# Reg-LT.net
KiCad netlist of a schematic drawn in EAGLE
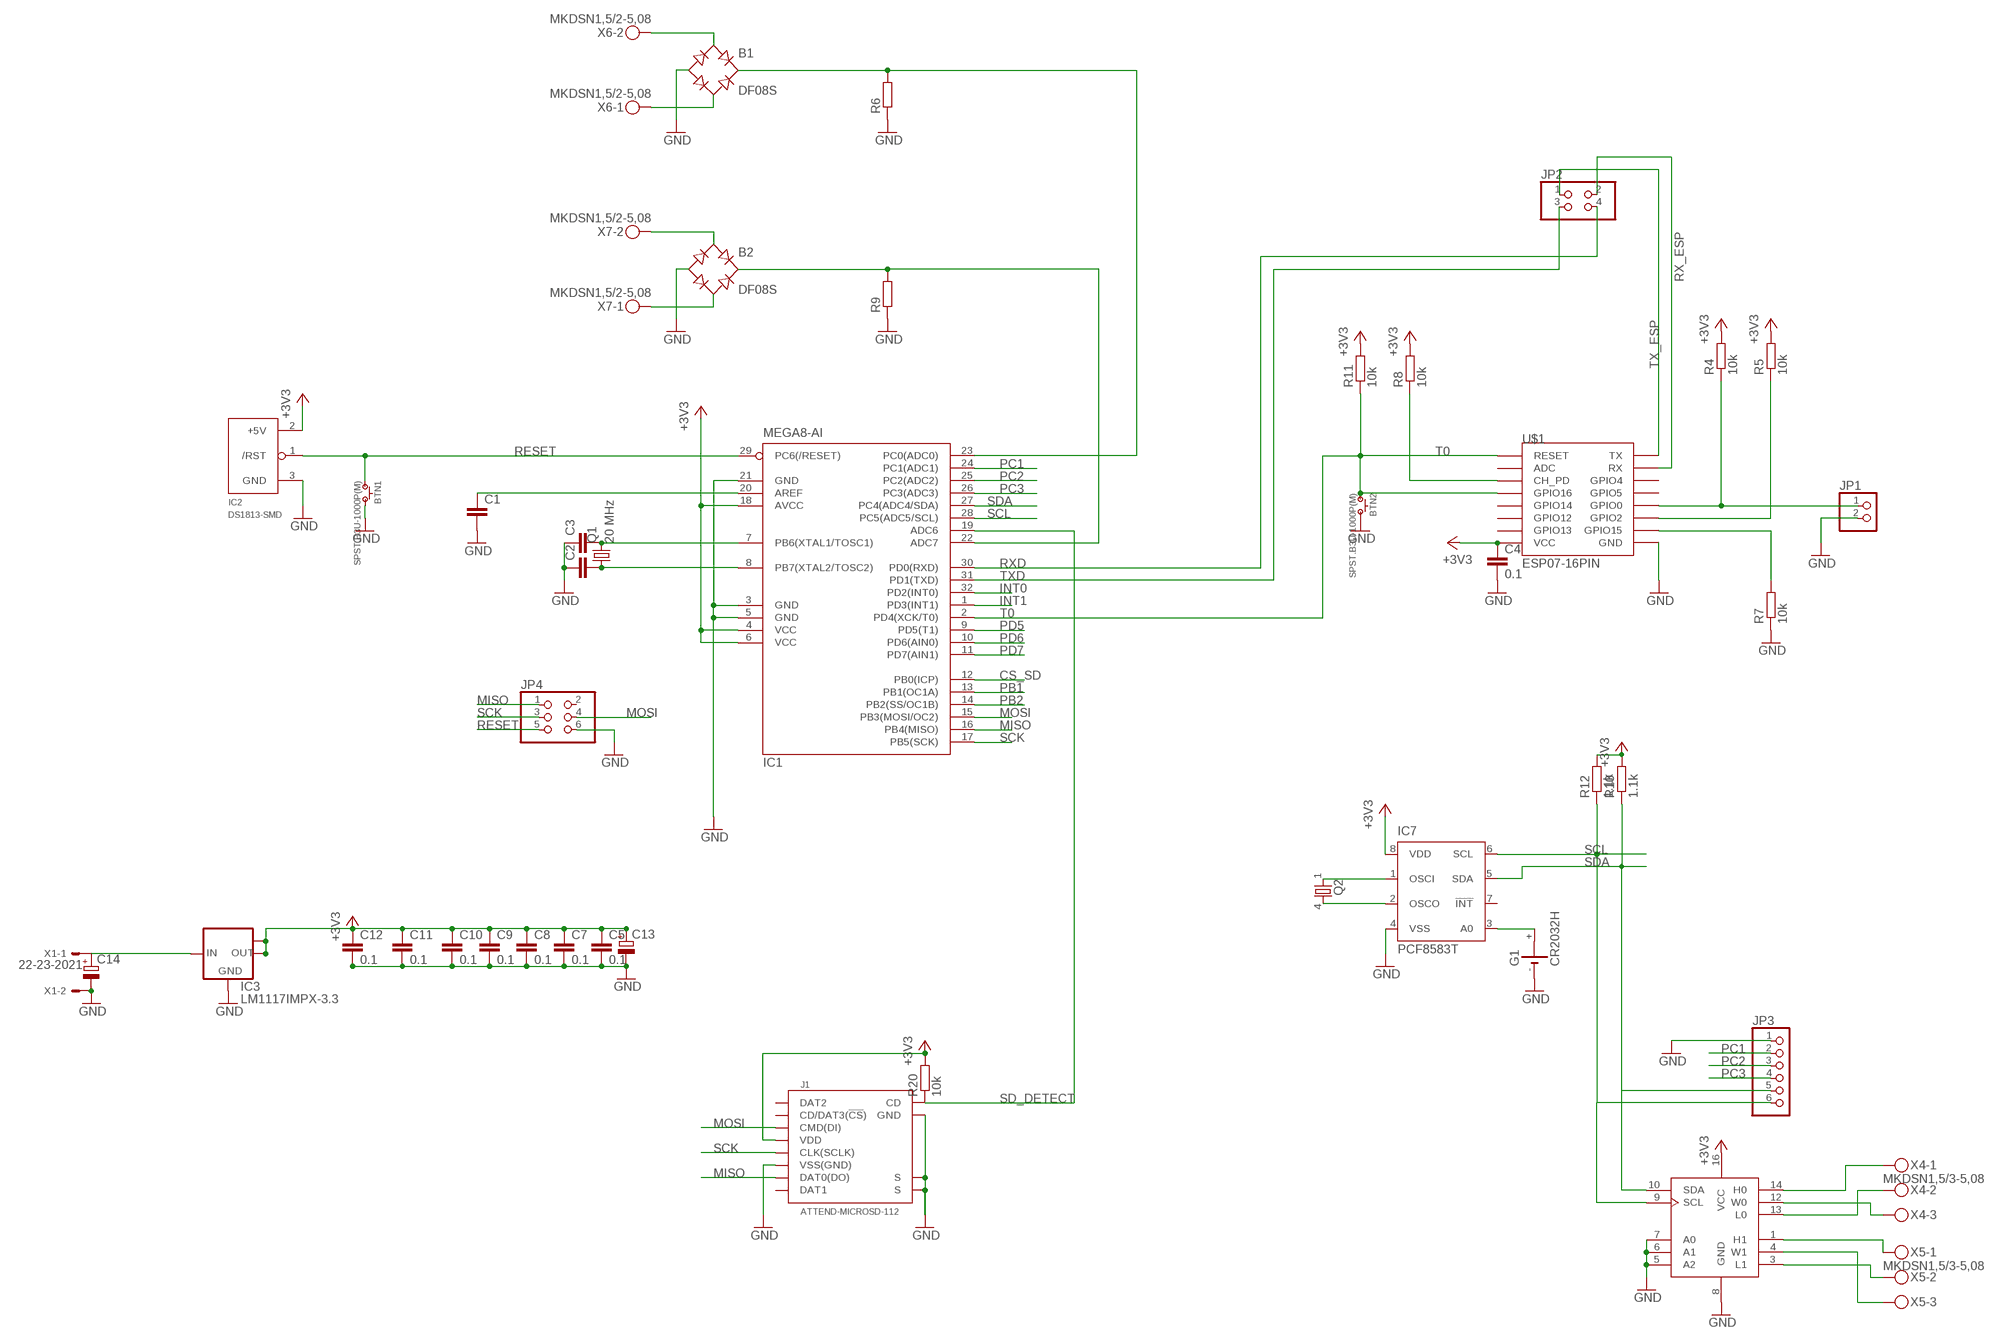
[diagram p0: schematic, sheet 1]

(export (version "E")
  (design (tool "Eeschema 10.0.6"))
  (components
    (comp (ref "B1")
      (value "DF08S")
      (footprint "eagle-import:DFS")
      (libsource (lib "eagle-import") (part "DFS08"))
    )
    (comp (ref "B2")
      (value "DF08S")
      (footprint "eagle-import:DFS")
      (libsource (lib "eagle-import") (part "DFS08"))
    )
    (comp (ref "BTN1")
      (value "SPST.B3U-1000P(M)")
      (footprint "eagle-import:B3U-1000P(M)")
      (libsource (lib "eagle-import") (part "SPST.B3U-1000P(M)"))
    )
    (comp (ref "BTN2")
      (value "SPST.B3U-1000P(M)")
      (footprint "eagle-import:B3U-1000P(M)")
      (libsource (lib "eagle-import") (part "SPST.B3U-1000P(M)"))
    )
    (comp (ref "C1")
      (value "C-EUC0805K")
      (footprint "eagle-import:C0805K")
      (libsource (lib "eagle-import") (part "C-EUC0805K"))
    )
    (comp (ref "C2")
      (value "C-EUC0805")
      (footprint "eagle-import:C0805")
      (libsource (lib "eagle-import") (part "C-EUC0805"))
    )
    (comp (ref "C3")
      (value "C-EUC0805")
      (footprint "eagle-import:C0805")
      (libsource (lib "eagle-import") (part "C-EUC0805"))
    )
    (comp (ref "C4")
      (value "0.1")
      (footprint "eagle-import:C0805")
      (libsource (lib "eagle-import") (part "C-EUC0805"))
    )
    (comp (ref "C5")
      (value "0.1")
      (footprint "eagle-import:C0805")
      (libsource (lib "eagle-import") (part "C-EUC0805"))
    )
    (comp (ref "C7")
      (value "0.1")
      (footprint "eagle-import:C0805")
      (libsource (lib "eagle-import") (part "C-EUC0805"))
    )
    (comp (ref "C8")
      (value "0.1")
      (footprint "eagle-import:C0805")
      (libsource (lib "eagle-import") (part "C-EUC0805"))
    )
    (comp (ref "C9")
      (value "0.1")
      (footprint "eagle-import:C0805")
      (libsource (lib "eagle-import") (part "C-EUC0805"))
    )
    (comp (ref "C10")
      (value "0.1")
      (footprint "eagle-import:C0805")
      (libsource (lib "eagle-import") (part "C-EUC0805"))
    )
    (comp (ref "C11")
      (value "0.1")
      (footprint "eagle-import:C0805")
      (libsource (lib "eagle-import") (part "C-EUC0805"))
    )
    (comp (ref "C12")
      (value "0.1")
      (footprint "eagle-import:C0805")
      (libsource (lib "eagle-import") (part "C-EUC0805"))
    )
    (comp (ref "C13")
      (value "CPOL-EU153CLV-0605")
      (footprint "eagle-import:153CLV-0605")
      (libsource (lib "eagle-import") (part "CPOL-EU153CLV-0605"))
    )
    (comp (ref "C14")
      (value "CPOL-EU153CLV-0605")
      (footprint "eagle-import:153CLV-0605")
      (libsource (lib "eagle-import") (part "CPOL-EU153CLV-0605"))
    )
    (comp (ref "G1")
      (value "CR2032H")
      (footprint "eagle-import:CR2032H")
      (libsource (lib "eagle-import") (part "CR2032H"))
    )
    (comp (ref "IC1")
      (value "MEGA8-AI")
      (footprint "eagle-import:TQFP32-08")
      (fields (field (name "MPN") "ATMEGA8-16AU"))
      (libsource (lib "eagle-import") (part "MEGA8-AI"))
    )
    (comp (ref "IC2")
      (value "DS1813-SMD")
      (footprint "eagle-import:SOT-23")
      (libsource (lib "eagle-import") (part "DS1813-SMD"))
    )
    (comp (ref "IC3")
      (value "LM1117IMPX-3.3")
      (footprint "eagle-import:SOT223")
      (libsource (lib "eagle-import") (part "LM1117IMPX-3.3"))
    )
    (comp (ref "IC7")
      (value "PCF8583T")
      (footprint "eagle-import:SO8-7_5")
      (libsource (lib "eagle-import") (part "PCF8583T"))
    )
    (comp (ref "J1")
      (value "ATTEND-MICROSD-112")
      (footprint "eagle-import:ATTEND-112")
      (libsource (lib "eagle-import") (part "ATTEND-MICROSD-112"))
    )
    (comp (ref "JP1")
      (value "PINHD-1X2")
      (footprint "eagle-import:1X02")
      (libsource (lib "eagle-import") (part "PINHD-1X2"))
    )
    (comp (ref "JP2")
      (value "PINHD-2X2")
      (footprint "eagle-import:2X02")
      (libsource (lib "eagle-import") (part "PINHD-2X2"))
    )
    (comp (ref "JP3")
      (value "PINHD-1X6")
      (footprint "eagle-import:1X06")
      (libsource (lib "eagle-import") (part "PINHD-1X6"))
    )
    (comp (ref "JP4")
      (value "PINHD-2X3")
      (footprint "eagle-import:2X03")
      (libsource (lib "eagle-import") (part "PINHD-2X3"))
    )
    (comp (ref "Q1")
      (value "20 MHz")
      (footprint "eagle-import:SM49")
      (libsource (lib "eagle-import") (part "CRYSTALSM49"))
    )
    (comp (ref "Q2")
      (value "MA306")
      (footprint "eagle-import:MA306")
      (libsource (lib "eagle-import") (part "MA306"))
    )
    (comp (ref "R4")
      (value "10k")
      (footprint "eagle-import:R0805")
      (libsource (lib "eagle-import") (part "R-EU_R0805"))
    )
    (comp (ref "R5")
      (value "10k")
      (footprint "eagle-import:R0805")
      (libsource (lib "eagle-import") (part "R-EU_R0805"))
    )
    (comp (ref "R6")
      (value "R-EU_VMTA55")
      (footprint "eagle-import:VMTA55")
      (libsource (lib "eagle-import") (part "R-EU_VMTA55"))
    )
    (comp (ref "R7")
      (value "10k")
      (footprint "eagle-import:R0805")
      (libsource (lib "eagle-import") (part "R-EU_R0805"))
    )
    (comp (ref "R8")
      (value "10k")
      (footprint "eagle-import:R0805")
      (libsource (lib "eagle-import") (part "R-EU_R0805"))
    )
    (comp (ref "R9")
      (value "R-EU_VMTA55")
      (footprint "eagle-import:VMTA55")
      (libsource (lib "eagle-import") (part "R-EU_VMTA55"))
    )
    (comp (ref "R10")
      (value "1.1k")
      (footprint "eagle-import:R0805")
      (libsource (lib "eagle-import") (part "R-EU_R0805"))
    )
    (comp (ref "R11")
      (value "10k")
      (footprint "eagle-import:R0805")
      (libsource (lib "eagle-import") (part "R-EU_R0805"))
    )
    (comp (ref "R12")
      (value "1.1k")
      (footprint "eagle-import:R0805")
      (libsource (lib "eagle-import") (part "R-EU_R0805"))
    )
    (comp (ref "R20")
      (value "10k")
      (footprint "eagle-import:R0805")
      (libsource (lib "eagle-import") (part "R-EU_R0805"))
    )
    (comp (ref "U$1")
      (value "ESP07-16PIN")
      (footprint "eagle-import:ESP07-16PIN")
      (libsource (lib "eagle-import") (part "ESP07-16PIN"))
    )
    (comp (ref "U$5")
      (value "DS1803ZSO16")
      (footprint "eagle-import:SO16")
      (libsource (lib "eagle-import") (part "DS1803ZSO16"))
    )
    (comp (ref "X1")
      (value "22-23-2021")
      (footprint "eagle-import:22-23-2021")
      (fields (field (name "MF") "MOLEX"))
      (libsource (lib "eagle-import") (part "22-23-2021"))
    )
    (comp (ref "X4")
      (value "MKDSN1,5/3-5,08")
      (footprint "eagle-import:MKDSN1,5_3-5,08")
      (libsource (lib "eagle-import") (part "MKDSN1,5/3-5,08"))
    )
    (comp (ref "X5")
      (value "MKDSN1,5/3-5,08")
      (footprint "eagle-import:MKDSN1,5_3-5,08")
      (libsource (lib "eagle-import") (part "MKDSN1,5/3-5,08"))
    )
    (comp (ref "X6")
      (value "MKDSN1,5/2-5,08")
      (footprint "eagle-import:MKDSN1,5_2-5,08")
      (libsource (lib "eagle-import") (part "MKDSN1,5/2-5,08"))
    )
    (comp (ref "X7")
      (value "MKDSN1,5/2-5,08")
      (footprint "eagle-import:MKDSN1,5_2-5,08")
      (libsource (lib "eagle-import") (part "MKDSN1,5/2-5,08"))
    )
  )
  (nets
    (net (code "1") (name "+3V3") (class "Default")
      (node (ref "C10") (pin "1") (pinfunction "1_1") (pintype "passive"))
      (node (ref "C11") (pin "1") (pinfunction "1_1") (pintype "passive"))
      (node (ref "C12") (pin "1") (pinfunction "1_1") (pintype "passive"))
      (node (ref "C13") (pin "+") (pinfunction "+_+") (pintype "passive"))
      (node (ref "C4") (pin "1") (pinfunction "1_1") (pintype "passive"))
      (node (ref "C5") (pin "1") (pinfunction "1_1") (pintype "passive"))
      (node (ref "C7") (pin "1") (pinfunction "1_1") (pintype "passive"))
      (node (ref "C8") (pin "1") (pinfunction "1_1") (pintype "passive"))
      (node (ref "C9") (pin "1") (pinfunction "1_1") (pintype "passive"))
      (node (ref "IC1") (pin "18") (pinfunction "AVCC_18") (pintype "power_in"))
      (node (ref "IC1") (pin "4") (pinfunction "VCC_4") (pintype "power_in"))
      (node (ref "IC1") (pin "6") (pinfunction "VCC_6") (pintype "power_in"))
      (node (ref "IC2") (pin "2") (pinfunction "+5V_2") (pintype "power_in"))
      (node (ref "IC3") (pin "2") (pinfunction "OUT_2") (pintype "passive"))
      (node (ref "IC3") (pin "TAB") (pinfunction "OUT1_TAB") (pintype "passive"))
      (node (ref "IC7") (pin "8") (pinfunction "VDD_8") (pintype "power_in"))
      (node (ref "J1") (pin "VDD") (pinfunction "VDD_VDD") (pintype "power_in"))
      (node (ref "R10") (pin "2") (pinfunction "2_2") (pintype "passive"))
      (node (ref "R11") (pin "2") (pinfunction "2_2") (pintype "passive"))
      (node (ref "R12") (pin "2") (pinfunction "2_2") (pintype "passive"))
      (node (ref "R20") (pin "2") (pinfunction "2_2") (pintype "passive"))
      (node (ref "R4") (pin "2") (pinfunction "2_2") (pintype "passive"))
      (node (ref "R5") (pin "2") (pinfunction "2_2") (pintype "passive"))
      (node (ref "R8") (pin "2") (pinfunction "2_2") (pintype "passive"))
      (node (ref "U$1") (pin "VCC") (pinfunction "VCC_VCC") (pintype "bidirectional"))
      (node (ref "U$5") (pin "16") (pinfunction "VCC_16") (pintype "power_in"))
    )
    (net (code "2") (name "/CS_SD") (class "Default")
      (node (ref "IC1") (pin "12") (pinfunction "PB0(ICP)_12") (pintype "bidirectional"))
    )
    (net (code "3") (name "/INT0") (class "Default")
      (node (ref "IC1") (pin "32") (pinfunction "PD2(INT0)_32") (pintype "bidirectional"))
    )
    (net (code "4") (name "/INT1") (class "Default")
      (node (ref "IC1") (pin "1") (pinfunction "PD3(INT1)_1") (pintype "bidirectional"))
    )
    (net (code "5") (name "/MISO") (class "Default")
      (node (ref "IC1") (pin "16") (pinfunction "PB4(MISO)_16") (pintype "bidirectional"))
      (node (ref "J1") (pin "DAT0") (pinfunction "DAT0(DO)_DAT0") (pintype "bidirectional"))
      (node (ref "JP4") (pin "1") (pinfunction "1_1") (pintype "passive"))
    )
    (net (code "6") (name "/MOSI") (class "Default")
      (node (ref "IC1") (pin "15") (pinfunction "PB3(MOSI/OC2)_15") (pintype "bidirectional"))
      (node (ref "J1") (pin "CMD") (pinfunction "CMD(DI)_CMD") (pintype "bidirectional"))
      (node (ref "JP4") (pin "4") (pinfunction "4_4") (pintype "passive"))
    )
    (net (code "7") (name "/PB1") (class "Default")
      (node (ref "IC1") (pin "13") (pinfunction "PB1(OC1A)_13") (pintype "bidirectional"))
    )
    (net (code "8") (name "/PB2") (class "Default")
      (node (ref "IC1") (pin "14") (pinfunction "PB2(SS/OC1B)_14") (pintype "bidirectional"))
    )
    (net (code "9") (name "/PC1") (class "Default")
      (node (ref "IC1") (pin "24") (pinfunction "PC1(ADC1)_24") (pintype "bidirectional"))
      (node (ref "JP3") (pin "2") (pinfunction "2_2") (pintype "passive"))
    )
    (net (code "10") (name "/PC2") (class "Default")
      (node (ref "IC1") (pin "25") (pinfunction "PC2(ADC2)_25") (pintype "bidirectional"))
      (node (ref "JP3") (pin "3") (pinfunction "3_3") (pintype "passive"))
    )
    (net (code "11") (name "/PC3") (class "Default")
      (node (ref "IC1") (pin "26") (pinfunction "PC3(ADC3)_26") (pintype "bidirectional"))
      (node (ref "JP3") (pin "4") (pinfunction "4_4") (pintype "passive"))
    )
    (net (code "12") (name "/PD5") (class "Default")
      (node (ref "IC1") (pin "9") (pinfunction "PD5(T1)_9") (pintype "bidirectional"))
    )
    (net (code "13") (name "/PD6") (class "Default")
      (node (ref "IC1") (pin "10") (pinfunction "PD6(AIN0)_10") (pintype "bidirectional"))
    )
    (net (code "14") (name "/PD7") (class "Default")
      (node (ref "IC1") (pin "11") (pinfunction "PD7(AIN1)_11") (pintype "bidirectional"))
    )
    (net (code "15") (name "/RESET") (class "Default")
      (node (ref "BTN1") (pin "1") (pinfunction "1_1") (pintype "bidirectional"))
      (node (ref "IC1") (pin "29") (pinfunction "PC6(/RESET)_29") (pintype "bidirectional"))
      (node (ref "IC2") (pin "1") (pinfunction "/RST_1") (pintype "passive"))
      (node (ref "JP4") (pin "5") (pinfunction "5_5") (pintype "passive"))
    )
    (net (code "16") (name "/RXD") (class "Default")
      (node (ref "IC1") (pin "30") (pinfunction "PD0(RXD)_30") (pintype "bidirectional"))
      (node (ref "JP2") (pin "4") (pinfunction "4_4") (pintype "passive"))
    )
    (net (code "17") (name "/RX_ESP") (class "Default")
      (node (ref "JP2") (pin "2") (pinfunction "2_2") (pintype "passive"))
      (node (ref "U$1") (pin "RX") (pinfunction "RX_RX") (pintype "bidirectional"))
    )
    (net (code "18") (name "/SCK") (class "Default")
      (node (ref "IC1") (pin "17") (pinfunction "PB5(SCK)_17") (pintype "bidirectional"))
      (node (ref "J1") (pin "CLK") (pinfunction "CLK(SCLK)_CLK") (pintype "bidirectional"))
      (node (ref "JP4") (pin "3") (pinfunction "3_3") (pintype "passive"))
    )
    (net (code "19") (name "/SCL") (class "Default")
      (node (ref "IC1") (pin "28") (pinfunction "PC5(ADC5/SCL)_28") (pintype "bidirectional"))
      (node (ref "IC7") (pin "6") (pinfunction "SCL_6") (pintype "input"))
      (node (ref "JP3") (pin "6") (pinfunction "6_6") (pintype "passive"))
      (node (ref "R12") (pin "1") (pinfunction "1_1") (pintype "passive"))
      (node (ref "U$5") (pin "9") (pinfunction "SCL_9") (pintype "input"))
    )
    (net (code "20") (name "/SDA") (class "Default")
      (node (ref "IC1") (pin "27") (pinfunction "PC4(ADC4/SDA)_27") (pintype "bidirectional"))
      (node (ref "IC7") (pin "5") (pinfunction "SDA_5") (pintype "bidirectional"))
      (node (ref "JP3") (pin "5") (pinfunction "5_5") (pintype "passive"))
      (node (ref "R10") (pin "1") (pinfunction "1_1") (pintype "passive"))
      (node (ref "U$5") (pin "10") (pinfunction "SDA_10") (pintype "input"))
    )
    (net (code "21") (name "/SD_DETECT") (class "Default")
      (node (ref "IC1") (pin "19") (pinfunction "ADC6_19") (pintype "bidirectional"))
      (node (ref "J1") (pin "CD") (pinfunction "CD_CD") (pintype "open_collector"))
      (node (ref "R20") (pin "1") (pinfunction "1_1") (pintype "passive"))
    )
    (net (code "22") (name "/T0") (class "Default")
      (node (ref "BTN2") (pin "1") (pinfunction "1_1") (pintype "bidirectional"))
      (node (ref "IC1") (pin "2") (pinfunction "PD4(XCK/T0)_2") (pintype "bidirectional"))
      (node (ref "R11") (pin "1") (pinfunction "1_1") (pintype "passive"))
      (node (ref "U$1") (pin "GPIO16") (pinfunction "GPIO16_GPIO16") (pintype "bidirectional"))
      (node (ref "U$1") (pin "REST") (pinfunction "RESET_REST") (pintype "bidirectional"))
    )
    (net (code "23") (name "/TXD") (class "Default")
      (node (ref "IC1") (pin "31") (pinfunction "PD1(TXD)_31") (pintype "bidirectional"))
      (node (ref "JP2") (pin "3") (pinfunction "3_3") (pintype "passive"))
    )
    (net (code "24") (name "/TX_ESP") (class "Default")
      (node (ref "JP2") (pin "1") (pinfunction "1_1") (pintype "passive"))
      (node (ref "U$1") (pin "TX") (pinfunction "TX_TX") (pintype "bidirectional"))
    )
    (net (code "25") (name "GND") (class "Default")
      (node (ref "B1") (pin "-") (pinfunction "-_-") (pintype "passive"))
      (node (ref "B2") (pin "-") (pinfunction "-_-") (pintype "passive"))
      (node (ref "BTN1") (pin "2") (pinfunction "2_2") (pintype "bidirectional"))
      (node (ref "BTN2") (pin "2") (pinfunction "2_2") (pintype "bidirectional"))
      (node (ref "C1") (pin "2") (pinfunction "2_2") (pintype "passive"))
      (node (ref "C10") (pin "2") (pinfunction "2_2") (pintype "passive"))
      (node (ref "C11") (pin "2") (pinfunction "2_2") (pintype "passive"))
      (node (ref "C12") (pin "2") (pinfunction "2_2") (pintype "passive"))
      (node (ref "C13") (pin "-") (pinfunction "-_-") (pintype "passive"))
      (node (ref "C14") (pin "-") (pinfunction "-_-") (pintype "passive"))
      (node (ref "C2") (pin "1") (pinfunction "1_1") (pintype "passive"))
      (node (ref "C3") (pin "1") (pinfunction "1_1") (pintype "passive"))
      (node (ref "C4") (pin "2") (pinfunction "2_2") (pintype "passive"))
      (node (ref "C5") (pin "2") (pinfunction "2_2") (pintype "passive"))
      (node (ref "C7") (pin "2") (pinfunction "2_2") (pintype "passive"))
      (node (ref "C8") (pin "2") (pinfunction "2_2") (pintype "passive"))
      (node (ref "C9") (pin "2") (pinfunction "2_2") (pintype "passive"))
      (node (ref "G1") (pin "-") (pinfunction "-_-") (pintype "passive"))
      (node (ref "IC1") (pin "21") (pinfunction "GND_21") (pintype "power_in"))
      (node (ref "IC1") (pin "3") (pinfunction "GND_3") (pintype "power_in"))
      (node (ref "IC1") (pin "5") (pinfunction "GND_5") (pintype "power_in"))
      (node (ref "IC2") (pin "3") (pinfunction "GND_3") (pintype "power_in"))
      (node (ref "IC3") (pin "1") (pinfunction "GND_1") (pintype "input"))
      (node (ref "IC7") (pin "4") (pinfunction "VSS_4") (pintype "power_in"))
      (node (ref "J1") (pin "GND") (pinfunction "GND_GND") (pintype "passive"))
      (node (ref "J1") (pin "S1") (pinfunction "S_S1") (pintype "passive"))
      (node (ref "J1") (pin "S2") (pinfunction "S_S2") (pintype "passive"))
      (node (ref "J1") (pin "VSS") (pinfunction "VSS(GND)_VSS") (pintype "power_in"))
      (node (ref "JP1") (pin "2") (pinfunction "2_2") (pintype "passive"))
      (node (ref "JP3") (pin "1") (pinfunction "1_1") (pintype "passive"))
      (node (ref "JP4") (pin "6") (pinfunction "6_6") (pintype "passive"))
      (node (ref "R6") (pin "1") (pinfunction "1_1") (pintype "passive"))
      (node (ref "R7") (pin "1") (pinfunction "1_1") (pintype "passive"))
      (node (ref "R9") (pin "1") (pinfunction "1_1") (pintype "passive"))
      (node (ref "U$1") (pin "GND") (pinfunction "GND_GND") (pintype "bidirectional"))
      (node (ref "U$5") (pin "5") (pinfunction "A2_5") (pintype "input"))
      (node (ref "U$5") (pin "6") (pinfunction "A1_6") (pintype "input"))
      (node (ref "U$5") (pin "7") (pinfunction "A0_7") (pintype "input"))
      (node (ref "U$5") (pin "8") (pinfunction "GND_8") (pintype "power_in"))
      (node (ref "X1") (pin "2") (pinfunction "S_2") (pintype "passive"))
    )
    (net (code "26") (name "Net-(IC1-ADC7)") (class "Default")
      (node (ref "B2") (pin "+") (pinfunction "+_+") (pintype "passive"))
      (node (ref "IC1") (pin "22") (pinfunction "ADC7_22") (pintype "bidirectional"))
      (node (ref "R9") (pin "2") (pinfunction "2_2") (pintype "passive"))
    )
    (net (code "27") (name "Net-(IC1-AREF)") (class "Default")
      (node (ref "C1") (pin "1") (pinfunction "1_1") (pintype "passive"))
      (node (ref "IC1") (pin "20") (pinfunction "AREF_20") (pintype "passive"))
    )
    (net (code "28") (name "Net-(IC1-PB6(XTAL1{slash}TOSC1))") (class "Default")
      (node (ref "C3") (pin "2") (pinfunction "2_2") (pintype "passive"))
      (node (ref "IC1") (pin "7") (pinfunction "PB6(XTAL1/TOSC1)_7") (pintype "bidirectional"))
      (node (ref "Q1") (pin "2") (pinfunction "2_2") (pintype "passive"))
    )
    (net (code "29") (name "Net-(IC1-PB7(XTAL2{slash}TOSC2))") (class "Default")
      (node (ref "C2") (pin "2") (pinfunction "2_2") (pintype "passive"))
      (node (ref "IC1") (pin "8") (pinfunction "PB7(XTAL2/TOSC2)_8") (pintype "bidirectional"))
      (node (ref "Q1") (pin "1") (pinfunction "1_1") (pintype "passive"))
    )
    (net (code "30") (name "Net-(IC1-PC0(ADC0))") (class "Default")
      (node (ref "B1") (pin "+") (pinfunction "+_+") (pintype "passive"))
      (node (ref "IC1") (pin "23") (pinfunction "PC0(ADC0)_23") (pintype "bidirectional"))
      (node (ref "R6") (pin "2") (pinfunction "2_2") (pintype "passive"))
    )
    (net (code "31") (name "Net-(IC3-IN)") (class "Default")
      (node (ref "C14") (pin "+") (pinfunction "+_+") (pintype "passive"))
      (node (ref "IC3") (pin "3") (pinfunction "IN_3") (pintype "input"))
      (node (ref "X1") (pin "1") (pinfunction "S_1") (pintype "passive"))
    )
    (net (code "32") (name "Net-(IC7-A0)") (class "Default")
      (node (ref "G1") (pin "+") (pinfunction "+_+") (pintype "passive"))
      (node (ref "IC7") (pin "3") (pinfunction "A0_3") (pintype "input"))
    )
    (net (code "33") (name "Net-(IC7-OSCI)") (class "Default")
      (node (ref "IC7") (pin "1") (pinfunction "OSCI_1") (pintype "input"))
      (node (ref "Q2") (pin "1") (pinfunction "1_1") (pintype "passive"))
    )
    (net (code "34") (name "Net-(IC7-OSCO)") (class "Default")
      (node (ref "IC7") (pin "2") (pinfunction "OSCO_2") (pintype "output"))
      (node (ref "Q2") (pin "4") (pinfunction "2_4") (pintype "passive"))
    )
    (net (code "35") (name "Net-(JP1-Pad1)") (class "Default")
      (node (ref "JP1") (pin "1") (pinfunction "1_1") (pintype "passive"))
      (node (ref "R4") (pin "1") (pinfunction "1_1") (pintype "passive"))
      (node (ref "U$1") (pin "GPIO0") (pinfunction "GPIO0_GPIO0") (pintype "bidirectional"))
    )
    (net (code "36") (name "Net-(R5-Pad1)") (class "Default")
      (node (ref "R5") (pin "1") (pinfunction "1_1") (pintype "passive"))
      (node (ref "U$1") (pin "GPIO2") (pinfunction "GPIO2_GPIO2") (pintype "bidirectional"))
    )
    (net (code "37") (name "Net-(R7-Pad2)") (class "Default")
      (node (ref "R7") (pin "2") (pinfunction "2_2") (pintype "passive"))
      (node (ref "U$1") (pin "GPIO15") (pinfunction "GPIO15_GPIO15") (pintype "bidirectional"))
    )
    (net (code "38") (name "Net-(R8-Pad1)") (class "Default")
      (node (ref "R8") (pin "1") (pinfunction "1_1") (pintype "passive"))
      (node (ref "U$1") (pin "CH_PD") (pinfunction "CH_PD_CH_PD") (pintype "bidirectional"))
    )
    (net (code "39") (name "Net-(U$5-H0)") (class "Default")
      (node (ref "U$5") (pin "14") (pinfunction "H0_14") (pintype "bidirectional"))
      (node (ref "X4") (pin "1") (pinfunction "KL_1") (pintype "passive"))
    )
    (net (code "40") (name "Net-(U$5-H1)") (class "Default")
      (node (ref "U$5") (pin "1") (pinfunction "H1_1") (pintype "bidirectional"))
      (node (ref "X5") (pin "1") (pinfunction "KL_1") (pintype "passive"))
    )
    (net (code "41") (name "Net-(U$5-L0)") (class "Default")
      (node (ref "U$5") (pin "13") (pinfunction "L0_13") (pintype "bidirectional"))
      (node (ref "X4") (pin "2") (pinfunction "KL_2") (pintype "passive"))
    )
    (net (code "42") (name "Net-(U$5-L1)") (class "Default")
      (node (ref "U$5") (pin "3") (pinfunction "L1_3") (pintype "bidirectional"))
      (node (ref "X5") (pin "2") (pinfunction "KL_2") (pintype "passive"))
    )
    (net (code "43") (name "Net-(U$5-W0)") (class "Default")
      (node (ref "U$5") (pin "12") (pinfunction "W0_12") (pintype "bidirectional"))
      (node (ref "X4") (pin "3") (pinfunction "KL_3") (pintype "passive"))
    )
    (net (code "44") (name "Net-(U$5-W1)") (class "Default")
      (node (ref "U$5") (pin "4") (pinfunction "W1_4") (pintype "bidirectional"))
      (node (ref "X5") (pin "3") (pinfunction "KL_3") (pintype "passive"))
    )
    (net (code "45") (name "Net-(X6A-KL)") (class "Default")
      (node (ref "B1") (pin "AC2") (pinfunction "AC2_AC2") (pintype "passive"))
      (node (ref "X6") (pin "1") (pinfunction "KL_1") (pintype "passive"))
    )
    (net (code "46") (name "Net-(X6B-KL)") (class "Default")
      (node (ref "B1") (pin "AC1") (pinfunction "AC1_AC1") (pintype "passive"))
      (node (ref "X6") (pin "2") (pinfunction "KL_2") (pintype "passive"))
    )
    (net (code "47") (name "Net-(X7A-KL)") (class "Default")
      (node (ref "B2") (pin "AC2") (pinfunction "AC2_AC2") (pintype "passive"))
      (node (ref "X7") (pin "1") (pinfunction "KL_1") (pintype "passive"))
    )
    (net (code "48") (name "Net-(X7B-KL)") (class "Default")
      (node (ref "B2") (pin "AC1") (pinfunction "AC1_AC1") (pintype "passive"))
      (node (ref "X7") (pin "2") (pinfunction "KL_2") (pintype "passive"))
    )
    (net (code "49") (name "unconnected-(IC7-~{INT}-Pad7)") (class "Default")
      (node (ref "IC7") (pin "7") (pinfunction "~{INT}_7") (pintype "open_collector"))
    )
    (net (code "50") (name "unconnected-(J1-CD{slash}DAT3(~{CS})-PadDAT3)") (class "Default")
      (node (ref "J1") (pin "DAT3") (pinfunction "CD/DAT3(~{CS})_DAT3") (pintype "bidirectional"))
    )
    (net (code "51") (name "unconnected-(J1-PadDAT1)") (class "Default")
      (node (ref "J1") (pin "DAT1") (pinfunction "DAT1_DAT1") (pintype "bidirectional"))
    )
    (net (code "52") (name "unconnected-(J1-PadDAT2)") (class "Default")
      (node (ref "J1") (pin "DAT2") (pinfunction "DAT2_DAT2") (pintype "bidirectional"))
    )
    (net (code "53") (name "unconnected-(JP4-Pad2)") (class "Default")
      (node (ref "JP4") (pin "2") (pinfunction "2_2") (pintype "passive"))
    )
    (net (code "54") (name "unconnected-(U$1-PadADC)") (class "Default")
      (node (ref "U$1") (pin "ADC") (pinfunction "ADC_ADC") (pintype "bidirectional"))
    )
    (net (code "55") (name "unconnected-(U$1-PadGPIO4)") (class "Default")
      (node (ref "U$1") (pin "GPIO4") (pinfunction "GPIO4_GPIO4") (pintype "bidirectional"))
    )
    (net (code "56") (name "unconnected-(U$1-PadGPIO5)") (class "Default")
      (node (ref "U$1") (pin "GPIO5") (pinfunction "GPIO5_GPIO5") (pintype "bidirectional"))
    )
    (net (code "57") (name "unconnected-(U$1-PadGPIO12)") (class "Default")
      (node (ref "U$1") (pin "GPIO12") (pinfunction "GPIO12_GPIO12") (pintype "bidirectional"))
    )
    (net (code "58") (name "unconnected-(U$1-PadGPIO13)") (class "Default")
      (node (ref "U$1") (pin "GPIO13") (pinfunction "GPIO13_GPIO13") (pintype "bidirectional"))
    )
    (net (code "59") (name "unconnected-(U$1-PadGPIO14)") (class "Default")
      (node (ref "U$1") (pin "GPIO14") (pinfunction "GPIO14_GPIO14") (pintype "bidirectional"))
    )
  )
)
